# uart_console.net
KiCad netlist of a schematic drawn in Altium Designer
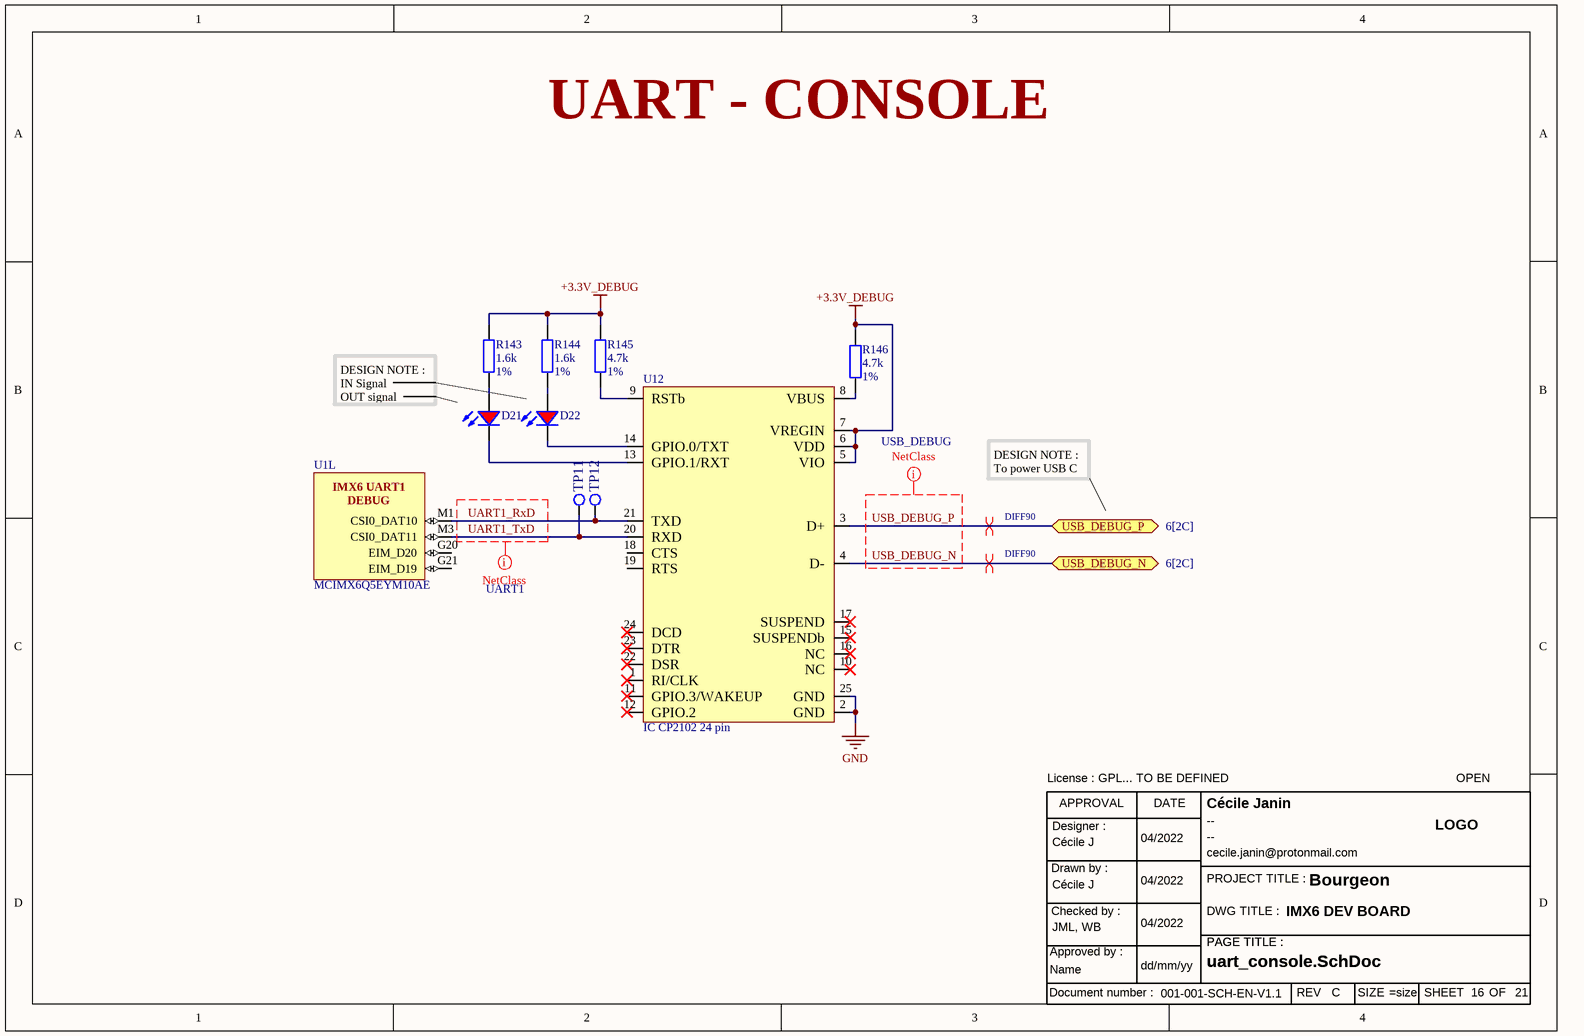
[diagram p0: uart_console.SchDoc]

(export (version "E")
  (design (tool "Eeschema 10.0.6"))
  (components
    (comp (ref "D21")
      (value "Red, 2V, 120deg")
      (footprint "LED red 0603")
      (description "WL-SMCC SMD Mono-color Chip LED Compact, size 0603, Red, 2V, 120deg 150060RS73220")
      (fields (field (name "PART NUMBER") "150060RS73220") (field (name "PUBLISHER") "Wurth Elektronik"))
      (libsource (lib "First Board IMX6") (part "LED Red 0603"))
    )
    (comp (ref "D22")
      (value "Red, 2V, 120deg")
      (footprint "LED red 0603")
      (description "WL-SMCC SMD Mono-color Chip LED Compact, size 0603, Red, 2V, 120deg 150060RS73220")
      (fields (field (name "PART NUMBER") "150060RS73220") (field (name "PUBLISHER") "Wurth Elektronik"))
      (libsource (lib "First Board IMX6") (part "LED Red 0603"))
    )
    (comp (ref "R143")
      (value "1.6k")
      (footprint "Res 0402/1005")
      (description "res 1.6k 1% 0402")
      (fields (field (name "POURCENTAGE") "1%"))
      (libsource (lib "First Board IMX6") (part "res 1.6k 1%"))
    )
    (comp (ref "R144")
      (value "1.6k")
      (footprint "Res 0402/1005")
      (description "res 1.6k 1% 0402")
      (fields (field (name "POURCENTAGE") "1%"))
      (libsource (lib "First Board IMX6") (part "res 1.6k 1%"))
    )
    (comp (ref "R145")
      (value "4.7k")
      (footprint "Res 0402/1005")
      (description "res 4.7k 1% 0402")
      (fields (field (name "POURCENTAGE") "1%"))
      (libsource (lib "First Board IMX6") (part "res 4.7k 1%"))
    )
    (comp (ref "R146")
      (value "4.7k")
      (footprint "Res 0402/1005")
      (description "res 4.7k 1% 0402")
      (fields (field (name "POURCENTAGE") "1%"))
      (libsource (lib "First Board IMX6") (part "res 4.7k 1%"))
    )
    (comp (ref "TB15")
      (value "Title bloc ANSI modified")
      (libsource (lib "First Board IMX6") (part "Title bloc ANSI"))
    )
    (comp (ref "TP11")
      (value "Test Point")
      (footprint "testpoint 1mm")
      (description "Test point 1mm diameter")
      (libsource (lib "First Board IMX6") (part "Test Point"))
    )
    (comp (ref "TP12")
      (value "Test Point")
      (footprint "testpoint 1mm")
      (description "Test point 1mm diameter")
      (libsource (lib "First Board IMX6") (part "Test Point"))
    )
    (comp (ref "U1")
      (value "MCIMX6Q5EYM10AE")
      (footprint "FRES-2197-01")
      (fields
        (field (name "PARTNUMBER") "MCIMX6Q5EYM10ACR")
        (field (name "MANUFACTURER") "Freescale Semiconductor")
      )
      (libsource (lib "First Board IMX6") (part "IMX6Q5EYM10AE"))
    )
    (comp (ref "U12")
      (value "IC CP2102 24 pin")
      (footprint "QFN24")
      (description "UART to USB converter")
      (libsource (lib "First Board IMX6") (part "IC CP2102 24 pin"))
    )
  )
  (nets
    (net (code "1") (name "+3.3V_DEBUG") (class "Default")
      (node (ref "R143") (pin "2") (pintype "passive"))
      (node (ref "R144") (pin "2") (pintype "passive"))
      (node (ref "R145") (pin "2") (pintype "passive"))
      (node (ref "R146") (pin "2") (pintype "passive"))
      (node (ref "U12") (pin "5") (pinfunction "VIO_5") (pintype "passive"))
      (node (ref "U12") (pin "6") (pinfunction "VDD_6") (pintype "passive"))
      (node (ref "U12") (pin "7") (pinfunction "VREGIN_7") (pintype "passive"))
    )
    (net (code "2") (name "/UART1_RxD") (class "Default")
      (node (ref "TP12") (pin "1") (pinfunction "tp_1") (pintype "passive"))
      (node (ref "U1") (pin "M1") (pinfunction "CSI0_DAT10_M1") (pintype "bidirectional"))
      (node (ref "U12") (pin "21") (pinfunction "TXD_21") (pintype "passive"))
    )
    (net (code "3") (name "/UART1_TxD") (class "Default")
      (node (ref "TP11") (pin "1") (pinfunction "tp_1") (pintype "passive"))
      (node (ref "U1") (pin "M3") (pinfunction "CSI0_DAT11_M3") (pintype "bidirectional"))
      (node (ref "U12") (pin "20") (pinfunction "RXD_20") (pintype "passive"))
    )
    (net (code "4") (name "/USB_DEBUG_N") (class "Default")
      (node (ref "U12") (pin "4") (pinfunction "D-_4") (pintype "passive"))
    )
    (net (code "5") (name "/USB_DEBUG_P") (class "Default")
      (node (ref "U12") (pin "3") (pinfunction "D+_3") (pintype "passive"))
    )
    (net (code "6") (name "GND") (class "Default")
      (node (ref "U12") (pin "2") (pinfunction "GND_2") (pintype "passive"))
      (node (ref "U12") (pin "25") (pinfunction "GND_25") (pintype "passive"))
    )
    (net (code "7") (name "Net-(D21-A)") (class "Default")
      (node (ref "D21") (pin "2") (pinfunction "A_2") (pintype "passive"))
      (node (ref "R143") (pin "1") (pintype "passive"))
    )
    (net (code "8") (name "Net-(D21-K)") (class "Default")
      (node (ref "D21") (pin "1") (pinfunction "K_1") (pintype "passive"))
      (node (ref "U12") (pin "13") (pinfunction "GPIO.1/RXT_13") (pintype "passive"))
    )
    (net (code "9") (name "Net-(D22-A)") (class "Default")
      (node (ref "D22") (pin "2") (pinfunction "A_2") (pintype "passive"))
      (node (ref "R144") (pin "1") (pintype "passive"))
    )
    (net (code "10") (name "Net-(D22-K)") (class "Default")
      (node (ref "D22") (pin "1") (pinfunction "K_1") (pintype "passive"))
      (node (ref "U12") (pin "14") (pinfunction "GPIO.0/TXT_14") (pintype "passive"))
    )
    (net (code "11") (name "Net-(U12-RSTb)") (class "Default")
      (node (ref "R145") (pin "1") (pintype "passive"))
      (node (ref "U12") (pin "9") (pinfunction "RSTb_9") (pintype "passive"))
    )
    (net (code "12") (name "Net-(U12-VBUS)") (class "Default")
      (node (ref "R146") (pin "1") (pintype "passive"))
      (node (ref "U12") (pin "8") (pinfunction "VBUS_8") (pintype "passive"))
    )
    (net (code "13") (name "unconnected-(U1L-EIM_D19-PadG21)") (class "Default")
      (node (ref "U1") (pin "G21") (pinfunction "EIM_D19_G21") (pintype "bidirectional"))
    )
    (net (code "14") (name "unconnected-(U1L-EIM_D20-PadG20)") (class "Default")
      (node (ref "U1") (pin "G20") (pinfunction "EIM_D20_G20") (pintype "bidirectional"))
    )
    (net (code "15") (name "unconnected-(U12-CTS-Pad18)") (class "Default")
      (node (ref "U12") (pin "18") (pinfunction "CTS_18") (pintype "passive"))
    )
    (net (code "16") (name "unconnected-(U12-DCD-Pad24)") (class "Default")
      (node (ref "U12") (pin "24") (pinfunction "DCD_24") (pintype "passive+no_connect"))
    )
    (net (code "17") (name "unconnected-(U12-DSR-Pad22)") (class "Default")
      (node (ref "U12") (pin "22") (pinfunction "DSR_22") (pintype "passive+no_connect"))
    )
    (net (code "18") (name "unconnected-(U12-DTR-Pad23)") (class "Default")
      (node (ref "U12") (pin "23") (pinfunction "DTR_23") (pintype "passive+no_connect"))
    )
    (net (code "19") (name "unconnected-(U12-GPIO.2-Pad12)") (class "Default")
      (node (ref "U12") (pin "12") (pinfunction "GPIO.2_12") (pintype "passive+no_connect"))
    )
    (net (code "20") (name "unconnected-(U12-GPIO.3{slash}WAKEUP-Pad11)") (class "Default")
      (node (ref "U12") (pin "11") (pinfunction "GPIO.3/WAKEUP_11") (pintype "passive+no_connect"))
    )
    (net (code "21") (name "unconnected-(U12-NC-Pad10)") (class "Default")
      (node (ref "U12") (pin "10") (pinfunction "NC_10") (pintype "passive+no_connect"))
    )
    (net (code "22") (name "unconnected-(U12-NC-Pad16)") (class "Default")
      (node (ref "U12") (pin "16") (pinfunction "NC_16") (pintype "passive+no_connect"))
    )
    (net (code "23") (name "unconnected-(U12-RI{slash}CLK-Pad1)") (class "Default")
      (node (ref "U12") (pin "1") (pinfunction "RI/CLK_1") (pintype "passive+no_connect"))
    )
    (net (code "24") (name "unconnected-(U12-RTS-Pad19)") (class "Default")
      (node (ref "U12") (pin "19") (pinfunction "RTS_19") (pintype "passive"))
    )
    (net (code "25") (name "unconnected-(U12-SUSPEND-Pad17)") (class "Default")
      (node (ref "U12") (pin "17") (pinfunction "SUSPEND_17") (pintype "passive+no_connect"))
    )
    (net (code "26") (name "unconnected-(U12-SUSPENDb-Pad15)") (class "Default")
      (node (ref "U12") (pin "15") (pinfunction "SUSPENDb_15") (pintype "passive+no_connect"))
    )
  )
)
